# Schematic.net
KiCad netlist of a schematic drawn in EasyEDA
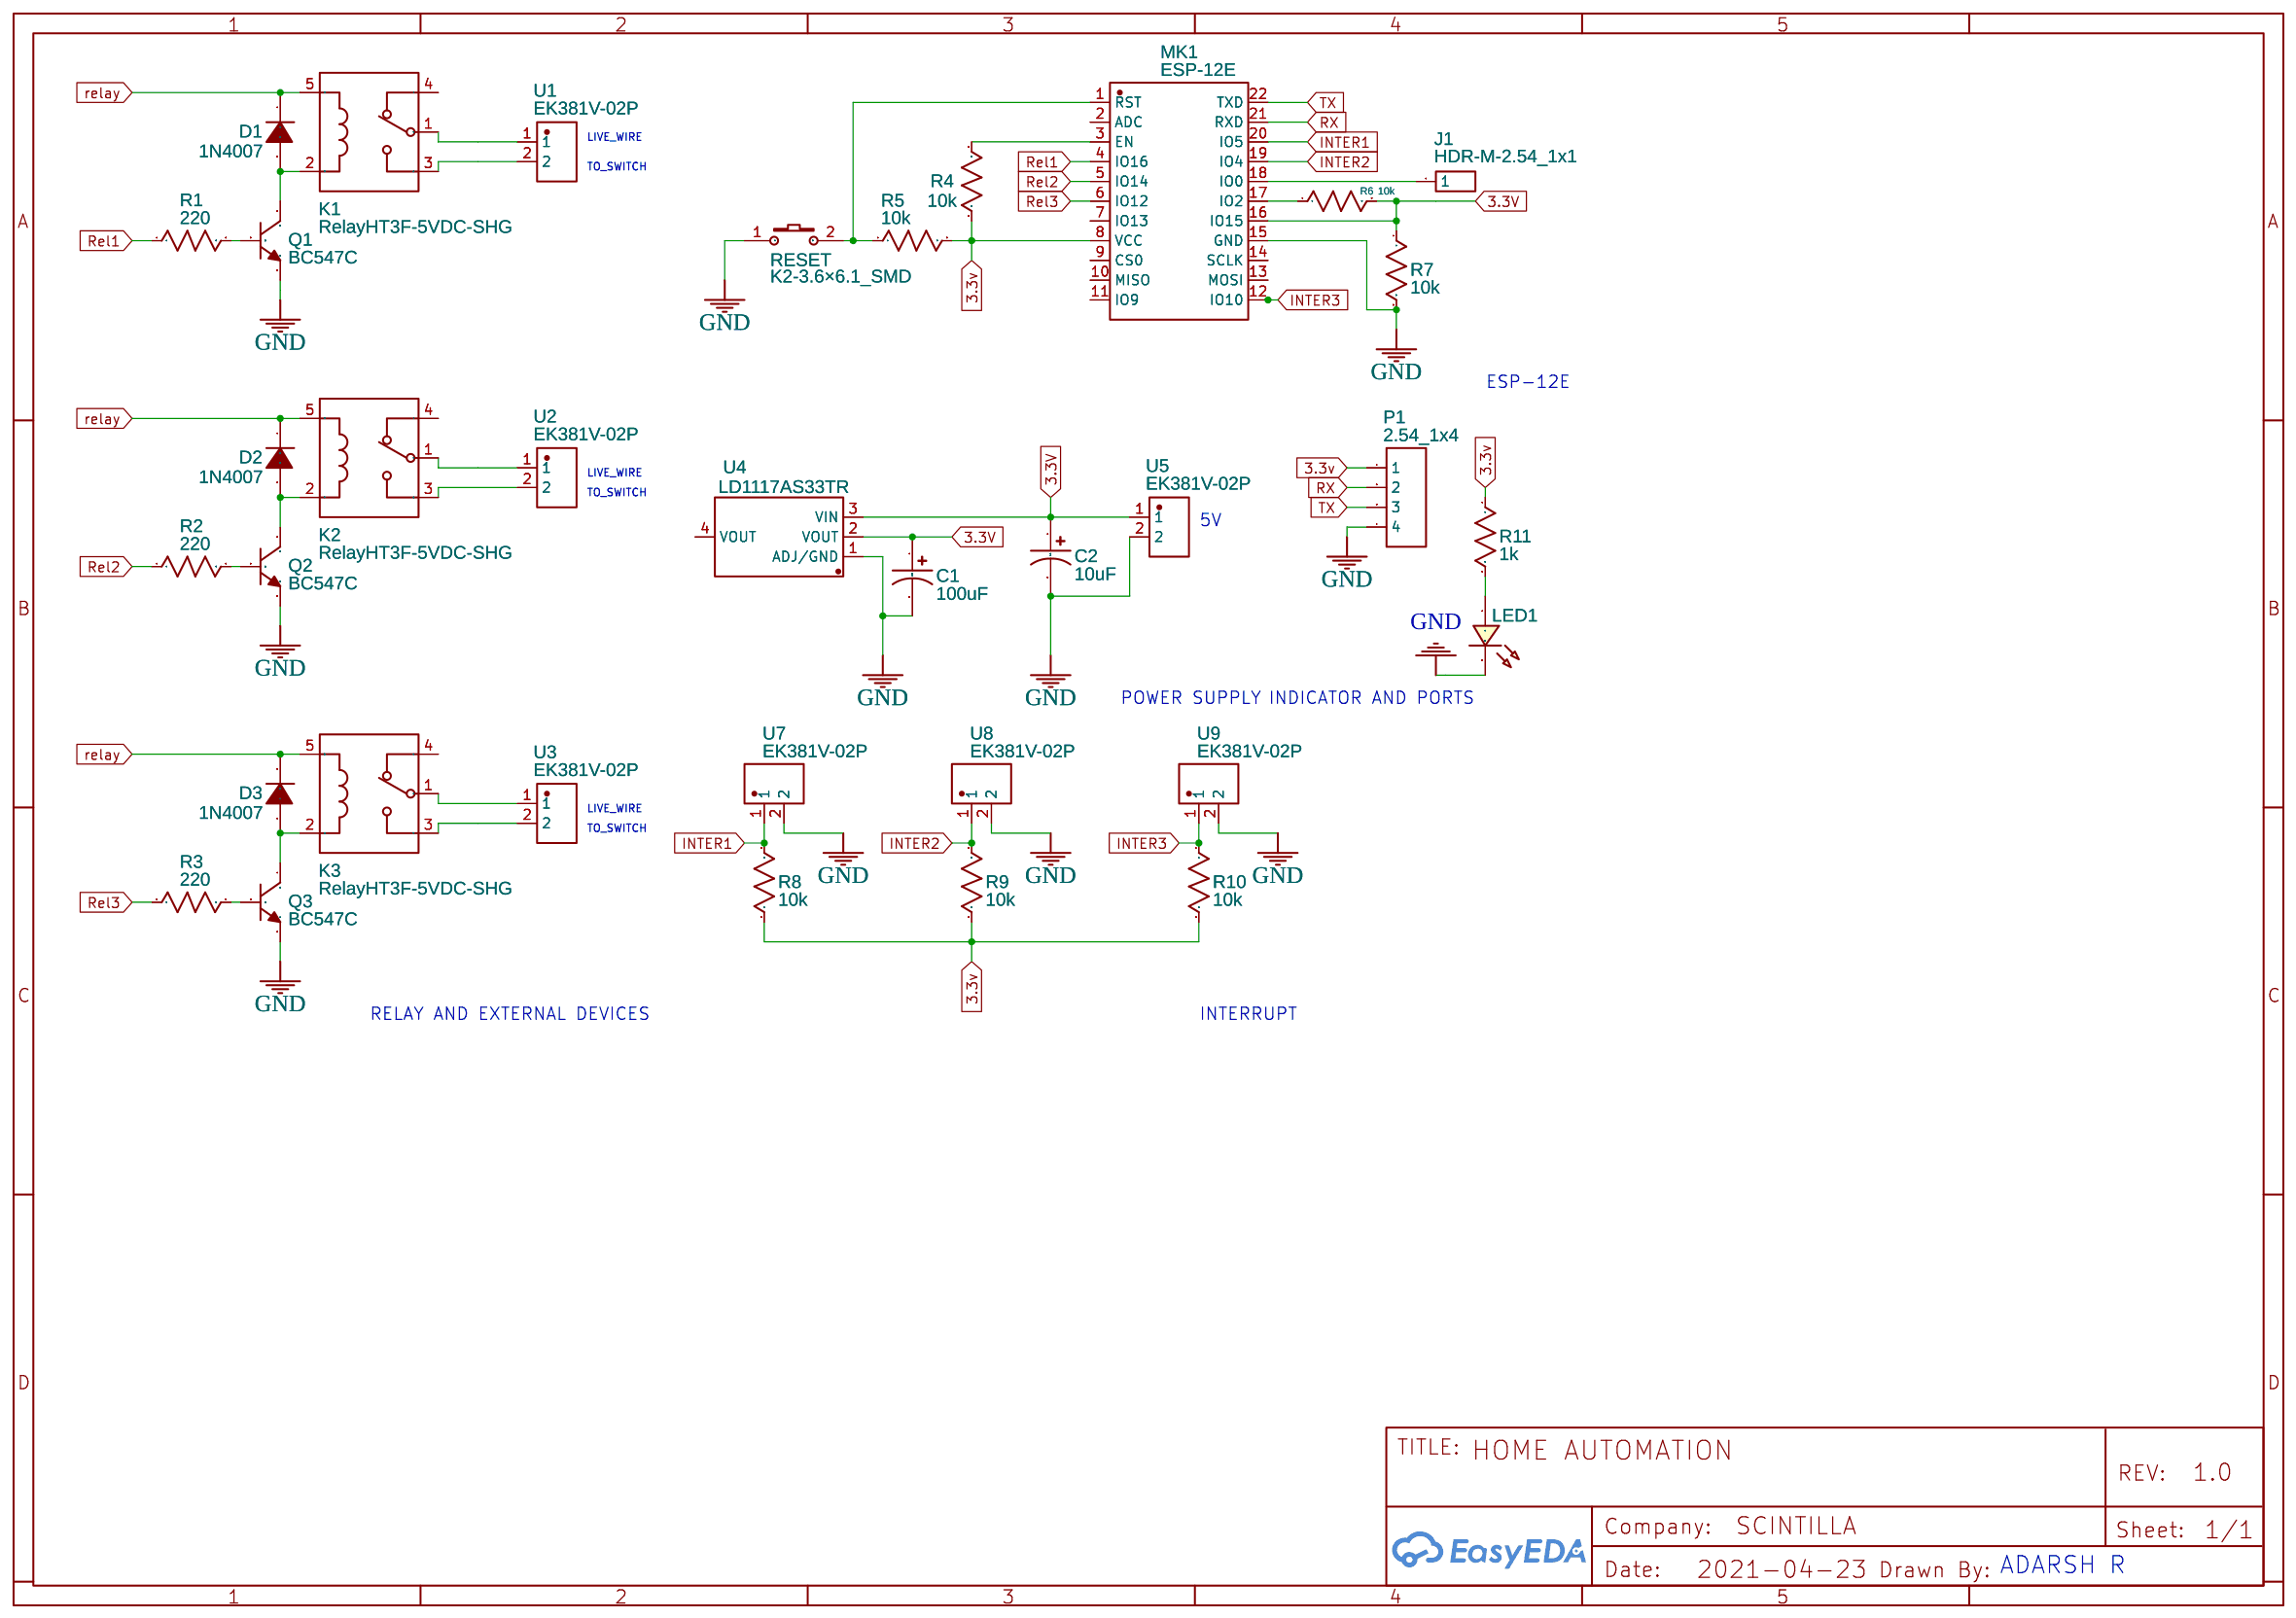
[diagram p0: schematic sheet]

(export (version "E")
  (design (tool "Eeschema 10.0.6"))
  (components
    (comp (ref "C1") (value "100uF") (libsource (lib "") (part "C_Tan_SMD_A_US")))
    (comp (ref "C2") (value "10uF") (libsource (lib "") (part "C_Tan_SMD_A_US")))
    (comp (ref "D1")
      (value "1N4007")
      (fields (field (name "BOM_Supplier Part") "C106903"))
      (libsource (lib "") (part "1N4007"))
    )
    (comp (ref "D2")
      (value "1N4007")
      (fields (field (name "BOM_Supplier Part") "C106903"))
      (libsource (lib "") (part "1N4007"))
    )
    (comp (ref "D3")
      (value "1N4007")
      (fields (field (name "BOM_Supplier Part") "C106903"))
      (libsource (lib "") (part "1N4007"))
    )
    (comp (ref "J1")
      (value "HDR-M-2.54_1x1")
      (fields (field (name "BOM_Supplier Part") "C81276"))
      (libsource (lib "") (part "HDR-M-2.54_1x1"))
    )
    (comp (ref "K1")
      (value "RelayHT3F-5VDC-SHG")
      (fields
        (field (name "BOM_Manufacturer Part") "RelayHT3F-12VDC-SHG")
        (field (name "BOM_Supplier Part") "C22022")
      )
      (libsource (lib "") (part "RelayHT3F-12VDC-SHG"))
    )
    (comp (ref "K2")
      (value "RelayHT3F-5VDC-SHG")
      (fields
        (field (name "BOM_Manufacturer Part") "RelayHT3F-12VDC-SHG")
        (field (name "BOM_Supplier Part") "C22022")
      )
      (libsource (lib "") (part "RelayHT3F-12VDC-SHG"))
    )
    (comp (ref "K3")
      (value "RelayHT3F-5VDC-SHG")
      (fields
        (field (name "BOM_Manufacturer Part") "RelayHT3F-12VDC-SHG")
        (field (name "BOM_Supplier Part") "C22022")
      )
      (libsource (lib "") (part "RelayHT3F-12VDC-SHG"))
    )
    (comp (ref "LED1")
      (value "LED-0603_R")
      (fields
        (field (name "BOM_Manufacturer Part") "19-217/R6C-AL1M2VY/3T")
        (field (name "BOM_Supplier Part") "C72044")
      )
      (libsource (lib "") (part "LED-0603_R"))
    )
    (comp (ref "MK1")
      (value "ESP-12E")
      (fields (field (name "BOM_Supplier Part") "C89297"))
      (libsource (lib "") (part "ESP-12E"))
    )
    (comp (ref "P1")
      (value "2.54_1x4")
      (fields
        (field (name "BOM_Manufacturer Part") "Header-Female-2.54_1x4")
        (field (name "BOM_Supplier Part") "C124413")
      )
      (libsource (lib "") (part "Header-Female-2.54_1x4"))
    )
    (comp (ref "Q1")
      (value "BC547C")
      (fields (field (name "BOM_Supplier Part") "C713614"))
      (libsource (lib "") (part "BC547C"))
    )
    (comp (ref "Q2")
      (value "BC547C")
      (fields (field (name "BOM_Supplier Part") "C713614"))
      (libsource (lib "") (part "BC547C"))
    )
    (comp (ref "Q3")
      (value "BC547C")
      (fields (field (name "BOM_Supplier Part") "C713614"))
      (libsource (lib "") (part "BC547C"))
    )
    (comp (ref "R1") (value "220") (libsource (lib "") (part "R_0603_US")))
    (comp (ref "R2") (value "220") (libsource (lib "") (part "R_0603_US")))
    (comp (ref "R3") (value "220") (libsource (lib "") (part "R_0603_US")))
    (comp (ref "R4") (value "10k") (libsource (lib "") (part "R_0603_US_1")))
    (comp (ref "R5") (value "10k") (libsource (lib "") (part "R_0603_US")))
    (comp (ref "R6") (value "10k") (libsource (lib "") (part "R_0603_US")))
    (comp (ref "R7") (value "10k") (libsource (lib "") (part "R_0603_US_2")))
    (comp (ref "R8") (value "10k") (libsource (lib "") (part "R_0603_US_1")))
    (comp (ref "R9") (value "10k") (libsource (lib "") (part "R_0603_US_1")))
    (comp (ref "R10") (value "10k") (libsource (lib "") (part "R_0603_US_2")))
    (comp (ref "R11") (value "1k") (libsource (lib "") (part "R_0603_US_2")))
    (comp (ref "RESET")
      (value "K2-3.6×6.1_SMD")
      (fields
        (field (name "BOM_Manufacturer Part") "K2-1107ST-A4SW-06")
        (field (name "BOM_Supplier Part") "C118141")
      )
      (libsource (lib "") (part "K2-3.6×6.1_SMD"))
    )
    (comp (ref "U1")
      (value "EK381V-02P")
      (fields (field (name "BOM_Supplier Part") "C192645"))
      (libsource (lib "") (part "EK381V-02P"))
    )
    (comp (ref "U2")
      (value "EK381V-02P")
      (fields (field (name "BOM_Supplier Part") "C192645"))
      (libsource (lib "") (part "EK381V-02P"))
    )
    (comp (ref "U3")
      (value "EK381V-02P")
      (fields (field (name "BOM_Supplier Part") "C192645"))
      (libsource (lib "") (part "EK381V-02P"))
    )
    (comp (ref "U4")
      (value "LD1117AS33TR")
      (fields (field (name "BOM_Supplier Part") "C115288"))
      (libsource (lib "") (part "LD1117AS33TR"))
    )
    (comp (ref "U5")
      (value "EK381V-02P")
      (fields (field (name "BOM_Supplier Part") "C192645"))
      (libsource (lib "") (part "EK381V-02P"))
    )
    (comp (ref "U7")
      (value "EK381V-02P")
      (fields (field (name "BOM_Supplier Part") "C192645"))
      (libsource (lib "") (part "EK381V-02P_1"))
    )
    (comp (ref "U8")
      (value "EK381V-02P")
      (fields (field (name "BOM_Supplier Part") "C192645"))
      (libsource (lib "") (part "EK381V-02P_1"))
    )
    (comp (ref "U9")
      (value "EK381V-02P")
      (fields (field (name "BOM_Supplier Part") "C192645"))
      (libsource (lib "") (part "EK381V-02P_1"))
    )
  )
  (nets
    (net (code "1") (name "3.3V") (class "Default")
      (node (ref "C1") (pin "1") (pinfunction "1_1") (pintype "unspecified"))
      (node (ref "C2") (pin "1") (pinfunction "1_1") (pintype "unspecified"))
      (node (ref "MK1") (pin "16") (pinfunction "IO15_16") (pintype "unspecified"))
      (node (ref "R6") (pin "2") (pinfunction "2_2") (pintype "unspecified"))
      (node (ref "R7") (pin "1") (pinfunction "1_1") (pintype "unspecified"))
      (node (ref "U4") (pin "2") (pinfunction "VOUT_2") (pintype "unspecified"))
      (node (ref "U4") (pin "3") (pinfunction "VIN_3") (pintype "unspecified"))
      (node (ref "U5") (pin "1") (pinfunction "1_1") (pintype "unspecified"))
    )
    (net (code "2") (name "3.3v") (class "Default")
      (node (ref "MK1") (pin "8") (pinfunction "VCC_8") (pintype "unspecified"))
      (node (ref "P1") (pin "1") (pinfunction "1_1") (pintype "input"))
      (node (ref "R10") (pin "2") (pinfunction "2_2") (pintype "unspecified"))
      (node (ref "R11") (pin "1") (pinfunction "1_1") (pintype "unspecified"))
      (node (ref "R4") (pin "1") (pinfunction "1_1") (pintype "unspecified"))
      (node (ref "R5") (pin "2") (pinfunction "2_2") (pintype "unspecified"))
      (node (ref "R8") (pin "1") (pinfunction "1_1") (pintype "unspecified"))
      (node (ref "R9") (pin "1") (pinfunction "1_1") (pintype "unspecified"))
    )
    (net (code "3") (name "GND") (class "Default")
      (node (ref "C1") (pin "2") (pinfunction "2_2") (pintype "unspecified"))
      (node (ref "C2") (pin "2") (pinfunction "2_2") (pintype "unspecified"))
      (node (ref "LED1") (pin "2") (pinfunction "2_2") (pintype "unspecified"))
      (node (ref "MK1") (pin "15") (pinfunction "GND_15") (pintype "unspecified"))
      (node (ref "P1") (pin "4") (pinfunction "4_4") (pintype "input"))
      (node (ref "Q1") (pin "3") (pinfunction "E_3") (pintype "input"))
      (node (ref "Q2") (pin "3") (pinfunction "E_3") (pintype "input"))
      (node (ref "Q3") (pin "3") (pinfunction "E_3") (pintype "input"))
      (node (ref "R7") (pin "2") (pinfunction "2_2") (pintype "unspecified"))
      (node (ref "RESET") (pin "1") (pinfunction "1_1") (pintype "unspecified"))
      (node (ref "U4") (pin "1") (pinfunction "ADJ/GND_1") (pintype "unspecified"))
      (node (ref "U5") (pin "2") (pinfunction "2_2") (pintype "unspecified"))
      (node (ref "U7") (pin "2") (pinfunction "2_2") (pintype "unspecified"))
      (node (ref "U8") (pin "2") (pinfunction "2_2") (pintype "unspecified"))
      (node (ref "U9") (pin "2") (pinfunction "2_2") (pintype "unspecified"))
    )
    (net (code "4") (name "INTER1") (class "Default")
      (node (ref "MK1") (pin "20") (pinfunction "IO5_20") (pintype "unspecified"))
      (node (ref "R8") (pin "2") (pinfunction "2_2") (pintype "unspecified"))
      (node (ref "U7") (pin "1") (pinfunction "1_1") (pintype "unspecified"))
    )
    (net (code "5") (name "INTER2") (class "Default")
      (node (ref "MK1") (pin "19") (pinfunction "IO4_19") (pintype "unspecified"))
      (node (ref "R9") (pin "2") (pinfunction "2_2") (pintype "unspecified"))
      (node (ref "U8") (pin "1") (pinfunction "1_1") (pintype "unspecified"))
    )
    (net (code "6") (name "INTER3") (class "Default")
      (node (ref "MK1") (pin "12") (pinfunction "IO10_12") (pintype "unspecified"))
      (node (ref "R10") (pin "1") (pinfunction "1_1") (pintype "unspecified"))
      (node (ref "U9") (pin "1") (pinfunction "1_1") (pintype "unspecified"))
    )
    (net (code "7") (name "Net-(D1-A)") (class "Default")
      (node (ref "D1") (pin "2") (pinfunction "A_2") (pintype "unspecified"))
      (node (ref "K1") (pin "2") (pinfunction "2_2") (pintype "unspecified"))
      (node (ref "Q1") (pin "1") (pinfunction "C_1") (pintype "input"))
    )
    (net (code "8") (name "Net-(D2-A)") (class "Default")
      (node (ref "D2") (pin "2") (pinfunction "A_2") (pintype "unspecified"))
      (node (ref "K2") (pin "2") (pinfunction "2_2") (pintype "unspecified"))
      (node (ref "Q2") (pin "1") (pinfunction "C_1") (pintype "input"))
    )
    (net (code "9") (name "Net-(D3-A)") (class "Default")
      (node (ref "D3") (pin "2") (pinfunction "A_2") (pintype "unspecified"))
      (node (ref "K3") (pin "2") (pinfunction "2_2") (pintype "unspecified"))
      (node (ref "Q3") (pin "1") (pinfunction "C_1") (pintype "input"))
    )
    (net (code "10") (name "Net-(K1-Pad1)") (class "Default")
      (node (ref "K1") (pin "1") (pinfunction "1_1") (pintype "unspecified"))
      (node (ref "U1") (pin "1") (pinfunction "1_1") (pintype "unspecified"))
    )
    (net (code "11") (name "Net-(K1-Pad3)") (class "Default")
      (node (ref "K1") (pin "3") (pinfunction "3_3") (pintype "unspecified"))
      (node (ref "U1") (pin "2") (pinfunction "2_2") (pintype "unspecified"))
    )
    (net (code "12") (name "Net-(K2-Pad1)") (class "Default")
      (node (ref "K2") (pin "1") (pinfunction "1_1") (pintype "unspecified"))
      (node (ref "U2") (pin "1") (pinfunction "1_1") (pintype "unspecified"))
    )
    (net (code "13") (name "Net-(K2-Pad3)") (class "Default")
      (node (ref "K2") (pin "3") (pinfunction "3_3") (pintype "unspecified"))
      (node (ref "U2") (pin "2") (pinfunction "2_2") (pintype "unspecified"))
    )
    (net (code "14") (name "Net-(K3-Pad1)") (class "Default")
      (node (ref "K3") (pin "1") (pinfunction "1_1") (pintype "unspecified"))
      (node (ref "U3") (pin "1") (pinfunction "1_1") (pintype "unspecified"))
    )
    (net (code "15") (name "Net-(K3-Pad3)") (class "Default")
      (node (ref "K3") (pin "3") (pinfunction "3_3") (pintype "unspecified"))
      (node (ref "U3") (pin "2") (pinfunction "2_2") (pintype "unspecified"))
    )
    (net (code "16") (name "Net-(LED1-Pad1)") (class "Default")
      (node (ref "LED1") (pin "1") (pinfunction "1_1") (pintype "unspecified"))
      (node (ref "R11") (pin "2") (pinfunction "2_2") (pintype "unspecified"))
    )
    (net (code "17") (name "Net-(MK1-EN)") (class "Default")
      (node (ref "MK1") (pin "3") (pinfunction "EN_3") (pintype "unspecified"))
      (node (ref "R4") (pin "2") (pinfunction "2_2") (pintype "unspecified"))
    )
    (net (code "18") (name "Net-(MK1-IO0)") (class "Default")
      (node (ref "J1") (pin "1") (pinfunction "1_1") (pintype "input"))
      (node (ref "MK1") (pin "18") (pinfunction "IO0_18") (pintype "unspecified"))
    )
    (net (code "19") (name "Net-(MK1-IO2)") (class "Default")
      (node (ref "MK1") (pin "17") (pinfunction "IO2_17") (pintype "unspecified"))
      (node (ref "R6") (pin "1") (pinfunction "1_1") (pintype "unspecified"))
    )
    (net (code "20") (name "Net-(MK1-RST)") (class "Default")
      (node (ref "MK1") (pin "1") (pinfunction "RST_1") (pintype "unspecified"))
      (node (ref "R5") (pin "1") (pinfunction "1_1") (pintype "unspecified"))
      (node (ref "RESET") (pin "2") (pinfunction "2_2") (pintype "unspecified"))
    )
    (net (code "21") (name "Net-(Q1-B)") (class "Default")
      (node (ref "Q1") (pin "2") (pinfunction "B_2") (pintype "input"))
      (node (ref "R1") (pin "2") (pinfunction "2_2") (pintype "unspecified"))
    )
    (net (code "22") (name "Net-(Q2-B)") (class "Default")
      (node (ref "Q2") (pin "2") (pinfunction "B_2") (pintype "input"))
      (node (ref "R2") (pin "2") (pinfunction "2_2") (pintype "unspecified"))
    )
    (net (code "23") (name "Net-(Q3-B)") (class "Default")
      (node (ref "Q3") (pin "2") (pinfunction "B_2") (pintype "input"))
      (node (ref "R3") (pin "2") (pinfunction "2_2") (pintype "unspecified"))
    )
    (net (code "24") (name "RX") (class "Default")
      (node (ref "MK1") (pin "21") (pinfunction "RXD_21") (pintype "unspecified"))
      (node (ref "P1") (pin "2") (pinfunction "2_2") (pintype "input"))
    )
    (net (code "25") (name "Rel1") (class "Default")
      (node (ref "MK1") (pin "4") (pinfunction "IO16_4") (pintype "unspecified"))
      (node (ref "R1") (pin "1") (pinfunction "1_1") (pintype "unspecified"))
    )
    (net (code "26") (name "Rel2") (class "Default")
      (node (ref "MK1") (pin "5") (pinfunction "IO14_5") (pintype "unspecified"))
      (node (ref "R2") (pin "1") (pinfunction "1_1") (pintype "unspecified"))
    )
    (net (code "27") (name "Rel3") (class "Default")
      (node (ref "MK1") (pin "6") (pinfunction "IO12_6") (pintype "unspecified"))
      (node (ref "R3") (pin "1") (pinfunction "1_1") (pintype "unspecified"))
    )
    (net (code "28") (name "TX") (class "Default")
      (node (ref "MK1") (pin "22") (pinfunction "TXD_22") (pintype "unspecified"))
      (node (ref "P1") (pin "3") (pinfunction "3_3") (pintype "input"))
    )
    (net (code "29") (name "relay") (class "Default")
      (node (ref "D1") (pin "1") (pinfunction "K_1") (pintype "unspecified"))
      (node (ref "D2") (pin "1") (pinfunction "K_1") (pintype "unspecified"))
      (node (ref "D3") (pin "1") (pinfunction "K_1") (pintype "unspecified"))
      (node (ref "K1") (pin "5") (pinfunction "5_5") (pintype "unspecified"))
      (node (ref "K2") (pin "5") (pinfunction "5_5") (pintype "unspecified"))
      (node (ref "K3") (pin "5") (pinfunction "5_5") (pintype "unspecified"))
    )
    (net (code "30") (name "unconnected-(K1-Pad4)") (class "Default")
      (node (ref "K1") (pin "4") (pinfunction "4_4") (pintype "unspecified"))
    )
    (net (code "31") (name "unconnected-(K2-Pad4)") (class "Default")
      (node (ref "K2") (pin "4") (pinfunction "4_4") (pintype "unspecified"))
    )
    (net (code "32") (name "unconnected-(K3-Pad4)") (class "Default")
      (node (ref "K3") (pin "4") (pinfunction "4_4") (pintype "unspecified"))
    )
    (net (code "33") (name "unconnected-(MK1-ADC-Pad2)") (class "Default")
      (node (ref "MK1") (pin "2") (pinfunction "ADC_2") (pintype "unspecified"))
    )
    (net (code "34") (name "unconnected-(MK1-CS0-Pad9)") (class "Default")
      (node (ref "MK1") (pin "9") (pinfunction "CS0_9") (pintype "unspecified"))
    )
    (net (code "35") (name "unconnected-(MK1-IO9-Pad11)") (class "Default")
      (node (ref "MK1") (pin "11") (pinfunction "IO9_11") (pintype "unspecified"))
    )
    (net (code "36") (name "unconnected-(MK1-IO13-Pad7)") (class "Default")
      (node (ref "MK1") (pin "7") (pinfunction "IO13_7") (pintype "unspecified"))
    )
    (net (code "37") (name "unconnected-(MK1-MISO-Pad10)") (class "Default")
      (node (ref "MK1") (pin "10") (pinfunction "MISO_10") (pintype "unspecified"))
    )
    (net (code "38") (name "unconnected-(MK1-MOSI-Pad13)") (class "Default")
      (node (ref "MK1") (pin "13") (pinfunction "MOSI_13") (pintype "unspecified"))
    )
    (net (code "39") (name "unconnected-(MK1-SCLK-Pad14)") (class "Default")
      (node (ref "MK1") (pin "14") (pinfunction "SCLK_14") (pintype "unspecified"))
    )
    (net (code "40") (name "unconnected-(U4-VOUT-Pad4)") (class "Default")
      (node (ref "U4") (pin "4") (pinfunction "VOUT_4") (pintype "unspecified"))
    )
  )
)
